# NAND.net
KiCad netlist of a schematic drawn in Altium Designer
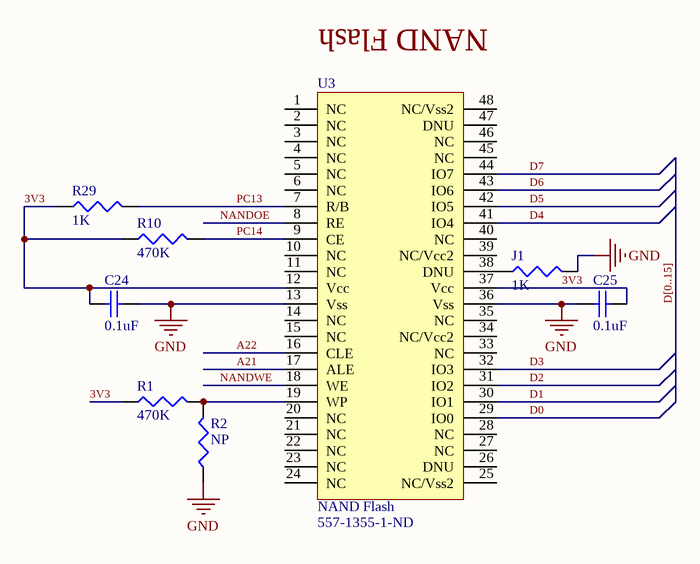
[diagram p0: NAND.SchDoc]

(export (version "E")
  (design (tool "Eeschema 10.0.6"))
  (components
    (comp (ref "C24")
      (value "0.1uF")
      (footprint "CAPC2008X06N")
      (description "CAP CER 0.1UF 50V 10% X7R 0805")
      (fields (field (name "Comment") "Kemet_0805_a_0.1uF"))
      (libsource (lib "Capacitors") (part "Kemet_0805_a_0.1uF"))
    )
    (comp (ref "C25")
      (value "0.1uF")
      (footprint "CAPC2008X06N")
      (description "CAP CER 0.1UF 50V 10% X7R 0805")
      (fields (field (name "Comment") "Kemet_0805_a_0.1uF"))
      (libsource (lib "Capacitors") (part "Kemet_0805_a_0.1uF"))
    )
    (comp (ref "J1")
      (value "1K")
      (footprint "RES0805")
      (description "RES 1.0K OHM 1/10W .5% 0805 SMD")
      (fields (field (name "Comment") "Susumu_0805_b1_1K"))
      (libsource (lib "Resistors") (part "Susumu_0805_b1_1K"))
    )
    (comp (ref "R1")
      (value "470K")
      (footprint "RES0805")
      (description "RES 470K OHM 1/10W .5% 0805 SMD")
      (fields (field (name "Comment") "Susumu_0805_b3_470K"))
      (libsource (lib "Resistors") (part "Susumu_0805_b3_470K"))
    )
    (comp (ref "R2")
      (value "NP")
      (footprint "RES0805")
      (description "No populate")
      (fields (field (name "Comment") "0805_NP"))
      (libsource (lib "Resistors") (part "0805_NP"))
    )
    (comp (ref "R10")
      (value "470K")
      (footprint "RES0805")
      (description "RES 470K OHM 1/10W .5% 0805 SMD")
      (fields (field (name "Comment") "Susumu_0805_b3_470K"))
      (libsource (lib "Resistors") (part "Susumu_0805_b3_470K"))
    )
    (comp (ref "R29")
      (value "1K")
      (footprint "RES0805")
      (description "RES 1.0K OHM 1/10W .5% 0805 SMD")
      (fields (field (name "Comment") "Susumu_0805_b1_1K"))
      (libsource (lib "Resistors") (part "Susumu_0805_b1_1K"))
    )
    (comp (ref "U3")
      (value "NAND Flash")
      (footprint "NAND Flash")
      (description "NAND Flash TSOP48")
      (fields
        (field (name "MANUFACTURER") "Micron Technology INC.")
        (field (name "SUPPLIER PART NUMBER 1") "557-1355-1-ND")
      )
      (libsource (lib "Micron Technology") (part "NAND Flash"))
    )
  )
  (nets
    (net (code "9") (name "/3V3") (class "Default")
      (node (ref "C24") (pin "1") (pinfunction "1_1") (pintype "passive"))
      (node (ref "C25") (pin "2") (pinfunction "2_2") (pintype "passive"))
      (node (ref "R1") (pin "1") (pinfunction "1_1") (pintype "passive"))
      (node (ref "R10") (pin "1") (pinfunction "1_1") (pintype "passive"))
      (node (ref "R29") (pin "1") (pinfunction "1_1") (pintype "passive"))
      (node (ref "U3") (pin "12") (pinfunction "Vcc_12") (pintype "passive"))
      (node (ref "U3") (pin "37") (pinfunction "Vcc_37") (pintype "passive"))
    )
    (net (code "10") (name "/A21") (class "Default")
      (node (ref "U3") (pin "17") (pinfunction "ALE_17") (pintype "passive"))
    )
    (net (code "11") (name "/A22") (class "Default")
      (node (ref "U3") (pin "16") (pinfunction "CLE_16") (pintype "passive"))
    )
    (net (code "12") (name "/D0") (class "Default")
      (node (ref "U3") (pin "29") (pinfunction "IO0_29") (pintype "passive"))
    )
    (net (code "13") (name "/D1") (class "Default")
      (node (ref "U3") (pin "30") (pinfunction "IO1_30") (pintype "passive"))
    )
    (net (code "14") (name "/D2") (class "Default")
      (node (ref "U3") (pin "31") (pinfunction "IO2_31") (pintype "passive"))
    )
    (net (code "15") (name "/D3") (class "Default")
      (node (ref "U3") (pin "32") (pinfunction "IO3_32") (pintype "passive"))
    )
    (net (code "16") (name "/D4") (class "Default")
      (node (ref "U3") (pin "41") (pinfunction "IO4_41") (pintype "passive"))
    )
    (net (code "17") (name "/D5") (class "Default")
      (node (ref "U3") (pin "42") (pinfunction "IO5_42") (pintype "passive"))
    )
    (net (code "18") (name "/D6") (class "Default")
      (node (ref "U3") (pin "43") (pinfunction "IO6_43") (pintype "passive"))
    )
    (net (code "19") (name "/D7") (class "Default")
      (node (ref "U3") (pin "44") (pinfunction "IO7_44") (pintype "passive"))
    )
    (net (code "21") (name "/NANDOE") (class "Default")
      (node (ref "U3") (pin "8") (pinfunction "RE_8") (pintype "passive"))
    )
    (net (code "22") (name "/NANDWE") (class "Default")
      (node (ref "U3") (pin "18") (pinfunction "WE_18") (pintype "passive"))
    )
    (net (code "23") (name "/PC13") (class "Default")
      (node (ref "R29") (pin "2") (pinfunction "2_2") (pintype "passive"))
      (node (ref "U3") (pin "7") (pinfunction "R/B_7") (pintype "passive"))
    )
    (net (code "24") (name "/PC14") (class "Default")
      (node (ref "R10") (pin "2") (pinfunction "2_2") (pintype "passive"))
      (node (ref "U3") (pin "9") (pinfunction "CE_9") (pintype "passive"))
    )
    (net (code "25") (name "GND") (class "Default")
      (node (ref "C24") (pin "2") (pinfunction "2_2") (pintype "passive"))
      (node (ref "C25") (pin "1") (pinfunction "1_1") (pintype "passive"))
      (node (ref "J1") (pin "2") (pinfunction "2_2") (pintype "passive"))
      (node (ref "R2") (pin "1") (pinfunction "1_1") (pintype "passive"))
      (node (ref "U3") (pin "13") (pinfunction "Vss_13") (pintype "passive"))
      (node (ref "U3") (pin "36") (pinfunction "Vss_36") (pintype "passive"))
    )
    (net (code "26") (name "Net-(J1-Pad1)") (class "Default")
      (node (ref "J1") (pin "1") (pinfunction "1_1") (pintype "passive"))
      (node (ref "U3") (pin "38") (pinfunction "DNU_38") (pintype "passive"))
    )
    (net (code "27") (name "Net-(U3-WP)") (class "Default")
      (node (ref "R1") (pin "2") (pinfunction "2_2") (pintype "passive"))
      (node (ref "R2") (pin "2") (pinfunction "2_2") (pintype "passive"))
      (node (ref "U3") (pin "19") (pinfunction "WP_19") (pintype "passive"))
    )
    (net (code "28") (name "unconnected-(U3-DNU-Pad26)") (class "Default")
      (node (ref "U3") (pin "26") (pinfunction "DNU_26") (pintype "passive"))
    )
    (net (code "29") (name "unconnected-(U3-DNU-Pad47)") (class "Default")
      (node (ref "U3") (pin "47") (pinfunction "DNU_47") (pintype "passive"))
    )
    (net (code "30") (name "unconnected-(U3-NC-Pad1)") (class "Default")
      (node (ref "U3") (pin "1") (pinfunction "NC_1") (pintype "passive"))
    )
    (net (code "31") (name "unconnected-(U3-NC-Pad2)") (class "Default")
      (node (ref "U3") (pin "2") (pinfunction "NC_2") (pintype "passive"))
    )
    (net (code "32") (name "unconnected-(U3-NC-Pad3)") (class "Default")
      (node (ref "U3") (pin "3") (pinfunction "NC_3") (pintype "passive"))
    )
    (net (code "33") (name "unconnected-(U3-NC-Pad4)") (class "Default")
      (node (ref "U3") (pin "4") (pinfunction "NC_4") (pintype "passive"))
    )
    (net (code "34") (name "unconnected-(U3-NC-Pad5)") (class "Default")
      (node (ref "U3") (pin "5") (pinfunction "NC_5") (pintype "passive"))
    )
    (net (code "35") (name "unconnected-(U3-NC-Pad6)") (class "Default")
      (node (ref "U3") (pin "6") (pinfunction "NC_6") (pintype "passive"))
    )
    (net (code "36") (name "unconnected-(U3-NC-Pad10)") (class "Default")
      (node (ref "U3") (pin "10") (pinfunction "NC_10") (pintype "passive"))
    )
    (net (code "37") (name "unconnected-(U3-NC-Pad11)") (class "Default")
      (node (ref "U3") (pin "11") (pinfunction "NC_11") (pintype "passive"))
    )
    (net (code "38") (name "unconnected-(U3-NC-Pad14)") (class "Default")
      (node (ref "U3") (pin "14") (pinfunction "NC_14") (pintype "passive"))
    )
    (net (code "39") (name "unconnected-(U3-NC-Pad15)") (class "Default")
      (node (ref "U3") (pin "15") (pinfunction "NC_15") (pintype "passive"))
    )
    (net (code "40") (name "unconnected-(U3-NC-Pad20)") (class "Default")
      (node (ref "U3") (pin "20") (pinfunction "NC_20") (pintype "passive"))
    )
    (net (code "41") (name "unconnected-(U3-NC-Pad21)") (class "Default")
      (node (ref "U3") (pin "21") (pinfunction "NC_21") (pintype "passive"))
    )
    (net (code "42") (name "unconnected-(U3-NC-Pad22)") (class "Default")
      (node (ref "U3") (pin "22") (pinfunction "NC_22") (pintype "passive"))
    )
    (net (code "43") (name "unconnected-(U3-NC-Pad23)") (class "Default")
      (node (ref "U3") (pin "23") (pinfunction "NC_23") (pintype "passive"))
    )
    (net (code "44") (name "unconnected-(U3-NC-Pad24)") (class "Default")
      (node (ref "U3") (pin "24") (pinfunction "NC_24") (pintype "passive"))
    )
    (net (code "45") (name "unconnected-(U3-NC-Pad27)") (class "Default")
      (node (ref "U3") (pin "27") (pinfunction "NC_27") (pintype "passive"))
    )
    (net (code "46") (name "unconnected-(U3-NC-Pad28)") (class "Default")
      (node (ref "U3") (pin "28") (pinfunction "NC_28") (pintype "passive"))
    )
    (net (code "47") (name "unconnected-(U3-NC-Pad33)") (class "Default")
      (node (ref "U3") (pin "33") (pinfunction "NC_33") (pintype "passive"))
    )
    (net (code "48") (name "unconnected-(U3-NC-Pad35)") (class "Default")
      (node (ref "U3") (pin "35") (pinfunction "NC_35") (pintype "passive"))
    )
    (net (code "49") (name "unconnected-(U3-NC-Pad40)") (class "Default")
      (node (ref "U3") (pin "40") (pinfunction "NC_40") (pintype "passive"))
    )
    (net (code "50") (name "unconnected-(U3-NC-Pad45)") (class "Default")
      (node (ref "U3") (pin "45") (pinfunction "NC_45") (pintype "passive"))
    )
    (net (code "51") (name "unconnected-(U3-NC-Pad46)") (class "Default")
      (node (ref "U3") (pin "46") (pinfunction "NC_46") (pintype "passive"))
    )
    (net (code "52") (name "unconnected-(U3-NC{slash}Vcc2-Pad34)") (class "Default")
      (node (ref "U3") (pin "34") (pinfunction "NC/Vcc2_34") (pintype "passive"))
    )
    (net (code "53") (name "unconnected-(U3-NC{slash}Vcc2-Pad39)") (class "Default")
      (node (ref "U3") (pin "39") (pinfunction "NC/Vcc2_39") (pintype "passive"))
    )
    (net (code "54") (name "unconnected-(U3-NC{slash}Vss2-Pad25)") (class "Default")
      (node (ref "U3") (pin "25") (pinfunction "NC/Vss2_25") (pintype "passive"))
    )
    (net (code "55") (name "unconnected-(U3-NC{slash}Vss2-Pad48)") (class "Default")
      (node (ref "U3") (pin "48") (pinfunction "NC/Vss2_48") (pintype "passive"))
    )
  )
)
